# CNEPuckRevG_Drivers_1.net
KiCad netlist of a schematic drawn in Altium Designer
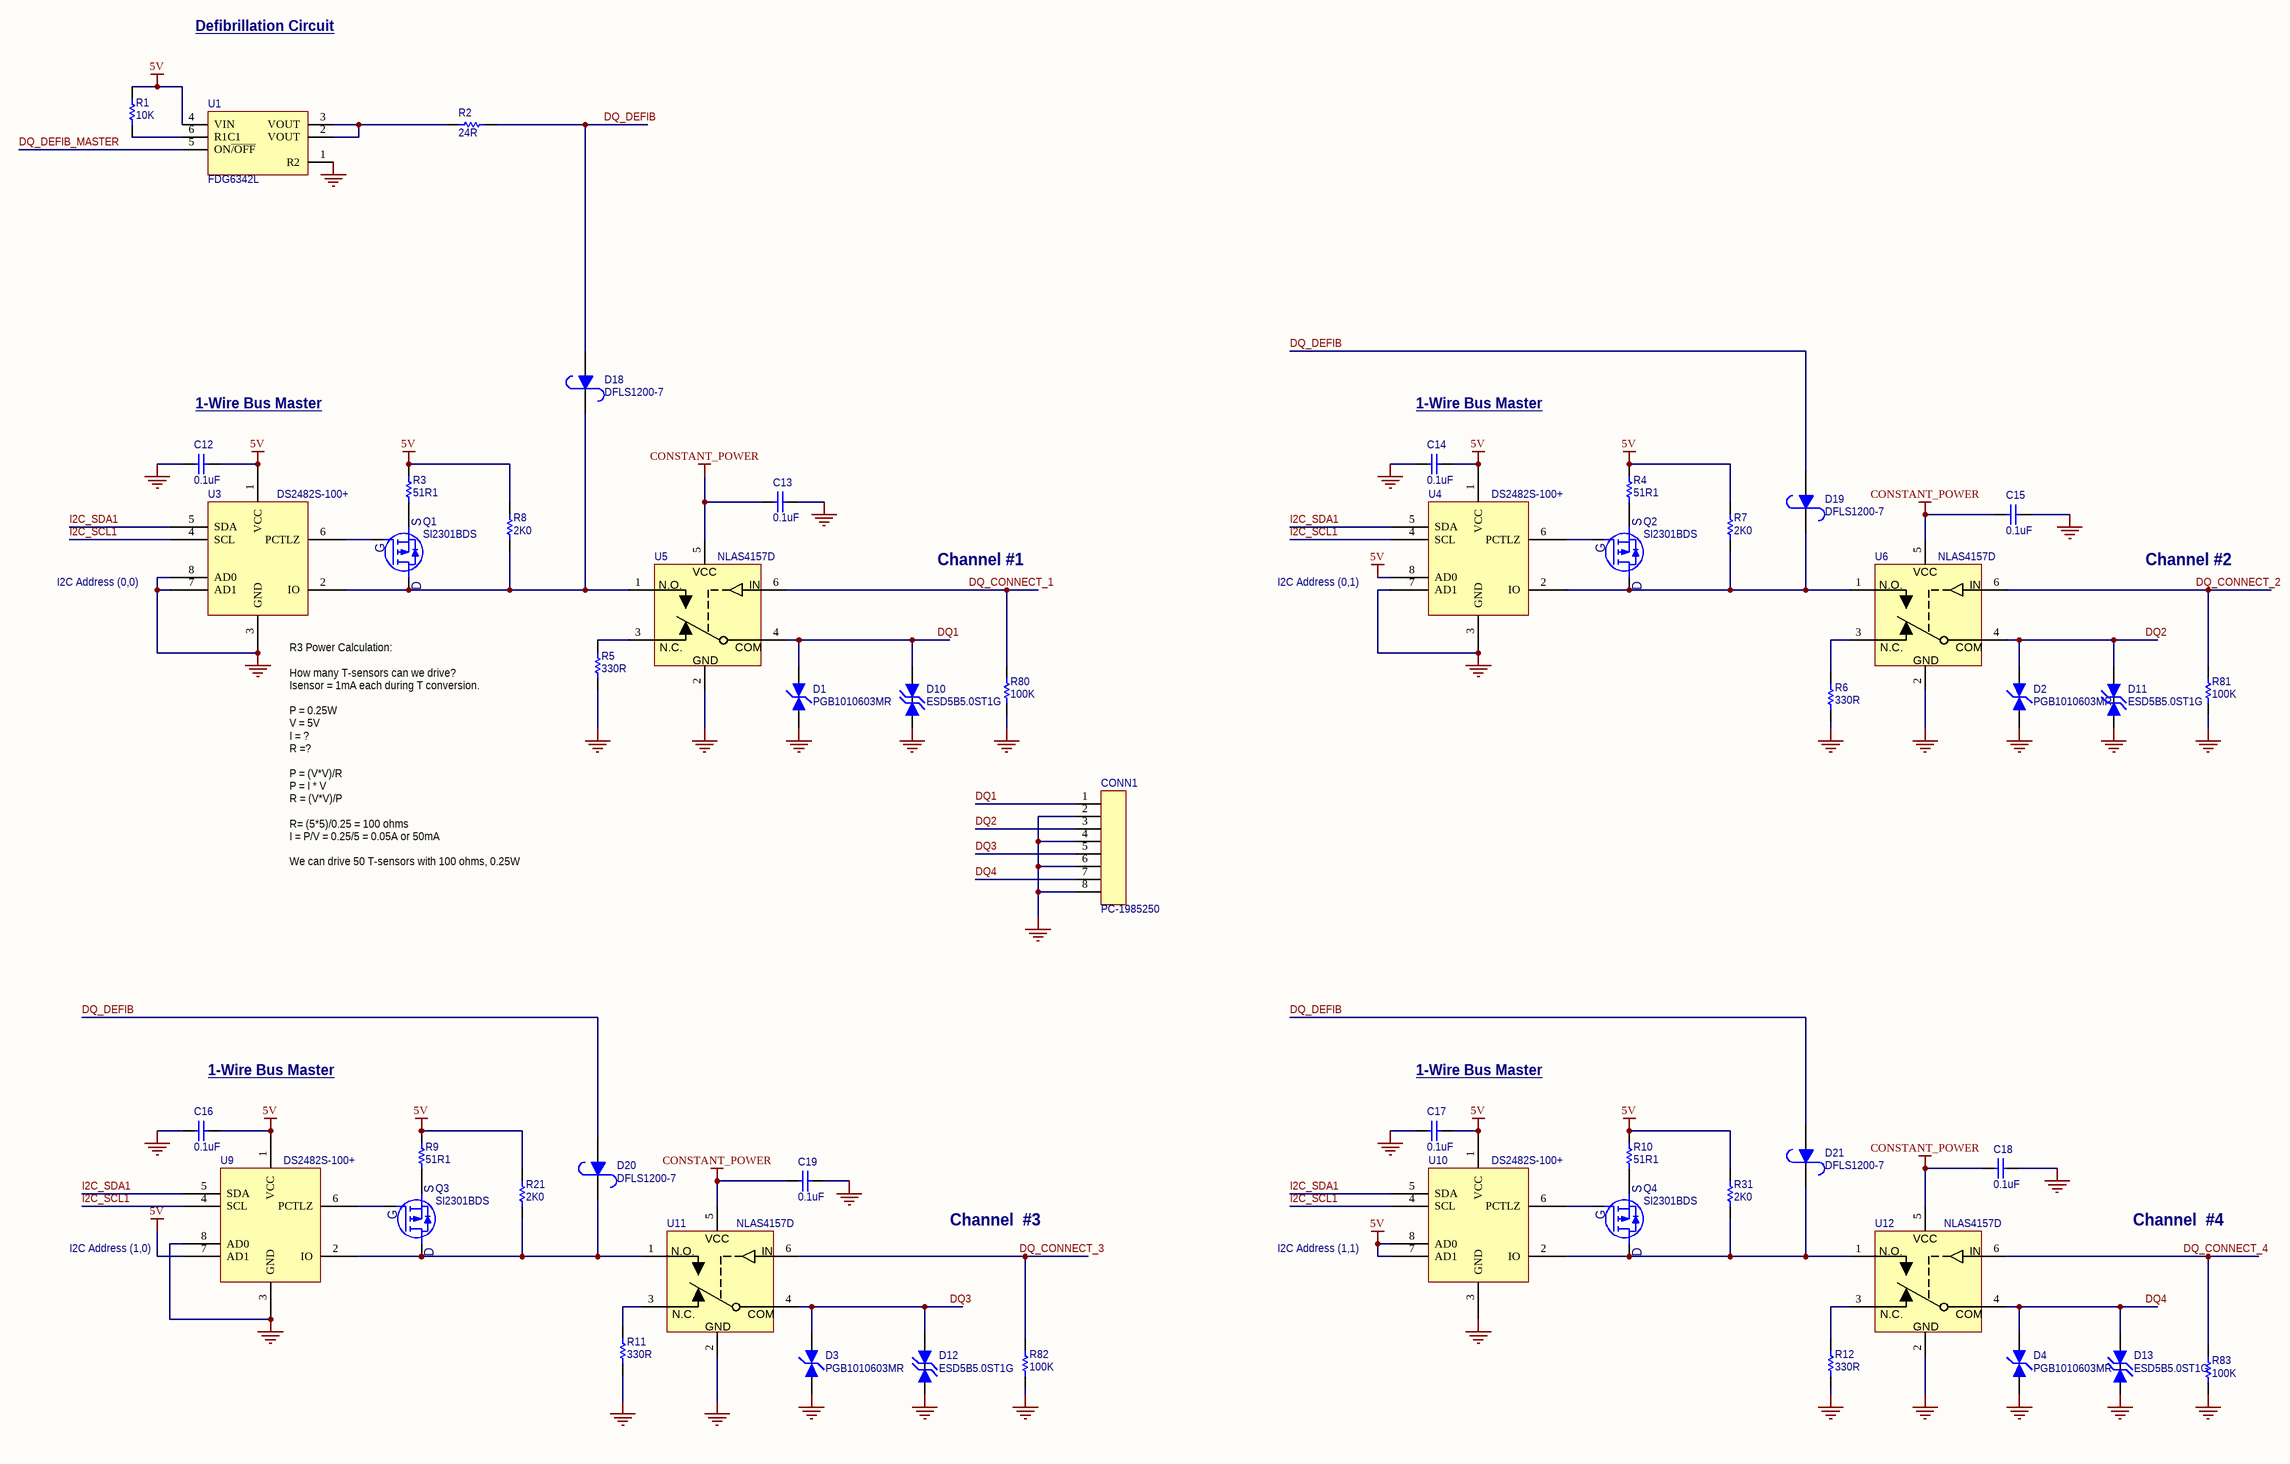
[diagram p0: CNEPuckRevG_Drivers_1.SchDoc]

(export (version "E")
  (design (tool "Eeschema 10.0.6"))
  (components
    (comp (ref "C12")
      (value "0.1uF")
      (footprint "RC0603")
      (description "CAP CERM .1UF 10% 16V X7R 0603")
      (fields (field (name "TOLERANCE") "±10%") (field (name "MANUFACTURER PART NUMBER") "0603YC104KAT2A"))
      (libsource (lib "Swage") (part "0603YC104KAT2A"))
    )
    (comp (ref "C13")
      (value "0.1uF")
      (footprint "RC0603")
      (description "CAP CERM .1UF 10% 16V X7R 0603")
      (fields (field (name "TOLERANCE") "±10%") (field (name "MANUFACTURER PART NUMBER") "0603YC104KAT2A"))
      (libsource (lib "Swage") (part "0603YC104KAT2A"))
    )
    (comp (ref "C14")
      (value "0.1uF")
      (footprint "RC0603")
      (description "CAP CERM .1UF 10% 16V X7R 0603")
      (fields (field (name "TOLERANCE") "±10%") (field (name "MANUFACTURER PART NUMBER") "0603YC104KAT2A"))
      (libsource (lib "Swage") (part "0603YC104KAT2A"))
    )
    (comp (ref "C15")
      (value "0.1uF")
      (footprint "RC0603")
      (description "CAP CERM .1UF 10% 16V X7R 0603")
      (fields (field (name "TOLERANCE") "±10%") (field (name "MANUFACTURER PART NUMBER") "0603YC104KAT2A"))
      (libsource (lib "Swage") (part "0603YC104KAT2A"))
    )
    (comp (ref "C16")
      (value "0.1uF")
      (footprint "RC0603")
      (description "CAP CERM .1UF 10% 16V X7R 0603")
      (fields (field (name "TOLERANCE") "±10%") (field (name "MANUFACTURER PART NUMBER") "0603YC104KAT2A"))
      (libsource (lib "Swage") (part "0603YC104KAT2A"))
    )
    (comp (ref "C17")
      (value "0.1uF")
      (footprint "RC0603")
      (description "CAP CERM .1UF 10% 16V X7R 0603")
      (fields (field (name "TOLERANCE") "±10%") (field (name "MANUFACTURER PART NUMBER") "0603YC104KAT2A"))
      (libsource (lib "Swage") (part "0603YC104KAT2A"))
    )
    (comp (ref "C18")
      (value "0.1uF")
      (footprint "RC0603")
      (description "CAP CERM .1UF 10% 16V X7R 0603")
      (fields (field (name "TOLERANCE") "±10%") (field (name "MANUFACTURER PART NUMBER") "0603YC104KAT2A"))
      (libsource (lib "Swage") (part "0603YC104KAT2A"))
    )
    (comp (ref "C19")
      (value "0.1uF")
      (footprint "RC0603")
      (description "CAP CERM .1UF 10% 16V X7R 0603")
      (fields (field (name "TOLERANCE") "±10%") (field (name "MANUFACTURER PART NUMBER") "0603YC104KAT2A"))
      (libsource (lib "Swage") (part "0603YC104KAT2A"))
    )
    (comp (ref "CONN1")
      (value "PC-1985250")
      (footprint "PTSA1.5/8-3.5-Z")
      (description "TERM BLOCK PCB 8POS 3.5MM GREEN")
      (fields
        (field (name "MANUFACTURER") "Phoenix Contact")
        (field (name "MANUFACTURER PART NUMBER") "1985250")
      )
      (libsource (lib "Swage") (part "1985250"))
    )
    (comp (ref "D1")
      (value "PGB1010603MR")
      (footprint "RC0603")
      (description "SUPPRESSOR ESD 24VDC 0603 SMD")
      (fields (field (name "MANUFACTURER") "Littelfuse Inc"))
      (libsource (lib "Swage") (part "PGB1010603MR"))
    )
    (comp (ref "D2")
      (value "PGB1010603MR")
      (footprint "RC0603")
      (description "SUPPRESSOR ESD 24VDC 0603 SMD")
      (fields (field (name "MANUFACTURER") "Littelfuse Inc"))
      (libsource (lib "Swage") (part "PGB1010603MR"))
    )
    (comp (ref "D3")
      (value "PGB1010603MR")
      (footprint "RC0603")
      (description "SUPPRESSOR ESD 24VDC 0603 SMD")
      (fields (field (name "MANUFACTURER") "Littelfuse Inc"))
      (libsource (lib "Swage") (part "PGB1010603MR"))
    )
    (comp (ref "D4")
      (value "PGB1010603MR")
      (footprint "RC0603")
      (description "SUPPRESSOR ESD 24VDC 0603 SMD")
      (fields (field (name "MANUFACTURER") "Littelfuse Inc"))
      (libsource (lib "Swage") (part "PGB1010603MR"))
    )
    (comp (ref "D10")
      (value "ESD5B5.0ST1G")
      (footprint "SOD-523")
      (description "TVS BIDIRECT 50W SOD523")
      (fields (field (name "MANUFACTURER") "ON Semiconductor"))
      (libsource (lib "Swage") (part "ESD5B5.0ST1G"))
    )
    (comp (ref "D11")
      (value "ESD5B5.0ST1G")
      (footprint "SOD-523")
      (description "TVS BIDIRECT 50W SOD523")
      (fields (field (name "MANUFACTURER") "ON Semiconductor"))
      (libsource (lib "Swage") (part "ESD5B5.0ST1G"))
    )
    (comp (ref "D12")
      (value "ESD5B5.0ST1G")
      (footprint "SOD-523")
      (description "TVS BIDIRECT 50W SOD523")
      (fields (field (name "MANUFACTURER") "ON Semiconductor"))
      (libsource (lib "Swage") (part "ESD5B5.0ST1G"))
    )
    (comp (ref "D13")
      (value "ESD5B5.0ST1G")
      (footprint "SOD-523")
      (description "TVS BIDIRECT 50W SOD523")
      (fields (field (name "MANUFACTURER") "ON Semiconductor"))
      (libsource (lib "Swage") (part "ESD5B5.0ST1G"))
    )
    (comp (ref "D18")
      (value "DFLS1200-7")
      (footprint "POWERDI-123")
      (description "DIODE SCHOTTKY 1A 200V PWRDI 123")
      (fields (field (name "MANUFACTURER") "Diodes Inc"))
      (libsource (lib "Swage") (part "DFLS1200-7"))
    )
    (comp (ref "D19")
      (value "DFLS1200-7")
      (footprint "POWERDI-123")
      (description "DIODE SCHOTTKY 1A 200V PWRDI 123")
      (fields (field (name "MANUFACTURER") "Diodes Inc"))
      (libsource (lib "Swage") (part "DFLS1200-7"))
    )
    (comp (ref "D20")
      (value "DFLS1200-7")
      (footprint "POWERDI-123")
      (description "DIODE SCHOTTKY 1A 200V PWRDI 123")
      (fields (field (name "MANUFACTURER") "Diodes Inc"))
      (libsource (lib "Swage") (part "DFLS1200-7"))
    )
    (comp (ref "D21")
      (value "DFLS1200-7")
      (footprint "POWERDI-123")
      (description "DIODE SCHOTTKY 1A 200V PWRDI 123")
      (fields (field (name "MANUFACTURER") "Diodes Inc"))
      (libsource (lib "Swage") (part "DFLS1200-7"))
    )
    (comp (ref "Q1")
      (value "SI2301BDS")
      (footprint "SOT23(DGS)")
      (description "MOSFET P-CH 20V 2.2A SOT23-3")
      (fields
        (field (name "MANUFACTURER") "Vishay/Siliconix")
        (field (name "MANUFACTURER PART NUMBER") "SI2301BDS-T1-E3")
      )
      (libsource (lib "Swage") (part "SI2301BDS-T1-E3"))
    )
    (comp (ref "Q2")
      (value "SI2301BDS")
      (footprint "SOT23(DGS)")
      (description "MOSFET P-CH 20V 2.2A SOT23-3")
      (fields
        (field (name "MANUFACTURER") "Vishay/Siliconix")
        (field (name "MANUFACTURER PART NUMBER") "SI2301BDS-T1-E3")
      )
      (libsource (lib "Swage") (part "SI2301BDS-T1-E3"))
    )
    (comp (ref "Q3")
      (value "SI2301BDS")
      (footprint "SOT23(DGS)")
      (description "MOSFET P-CH 20V 2.2A SOT23-3")
      (fields
        (field (name "MANUFACTURER") "Vishay/Siliconix")
        (field (name "MANUFACTURER PART NUMBER") "SI2301BDS-T1-E3")
      )
      (libsource (lib "Swage") (part "SI2301BDS-T1-E3"))
    )
    (comp (ref "Q4")
      (value "SI2301BDS")
      (footprint "SOT23(DGS)")
      (description "MOSFET P-CH 20V 2.2A SOT23-3")
      (fields
        (field (name "MANUFACTURER") "Vishay/Siliconix")
        (field (name "MANUFACTURER PART NUMBER") "SI2301BDS-T1-E3")
      )
      (libsource (lib "Swage") (part "SI2301BDS-T1-E3"))
    )
    (comp (ref "R1")
      (value "10K")
      (footprint "RC0603")
      (description "RES 10K OHM 1/10W 5% 0603 SMD")
      (fields
        (field (name "MANUFACTURER") "Panasonic Electronic Components")
        (field (name "MANUFACTURER PART NUMBER") "ERJ-3GEYJ103V")
      )
      (libsource (lib "Swage") (part "ERJ-3GEYJ103V"))
    )
    (comp (ref "R2")
      (value "24R")
      (footprint "RES2512")
      (description "RES 24 OHM 1W 5% 2512 SMD")
      (fields
        (field (name "MANUFACTURER") "Vishay/Dale")
        (field (name "MANUFACTURER PART NUMBER") "CRCW251224R0JNEG")
      )
      (libsource (lib "Swage") (part "RMCF2512JT24R0"))
    )
    (comp (ref "R3")
      (value "51R1")
      (footprint "RC0603")
      (description "RES 51.1 OHM .25W 1% 0603 SMD")
      (fields
        (field (name "MANUFACTURER") "Vishay Dale")
        (field (name "MANUFACTURER PART NUMBER") "CRCW060351R1FKEAHP")
      )
      (libsource (lib "Swage") (part "CRCW060351R1FKEAHP"))
    )
    (comp (ref "R4")
      (value "51R1")
      (footprint "RC0603")
      (description "RES 51.1 OHM .25W 1% 0603 SMD")
      (fields
        (field (name "MANUFACTURER") "Vishay Dale")
        (field (name "MANUFACTURER PART NUMBER") "CRCW060351R1FKEAHP")
      )
      (libsource (lib "Swage") (part "CRCW060351R1FKEAHP"))
    )
    (comp (ref "R5")
      (value "330R")
      (footprint "RC0805")
      (description "RES 330 OHM 1/8W 5% 0805 SMD")
      (fields
        (field (name "MANUFACTURER") "KOA Speer Technologies")
        (field (name "MANUFACTURER PART NUMBER") "RK73B2ATTD331J")
      )
      (libsource (lib "Swage") (part "ERJ-6GEYJ331V"))
    )
    (comp (ref "R6")
      (value "330R")
      (footprint "RC0805")
      (description "RES 330 OHM 1/8W 5% 0805 SMD")
      (fields
        (field (name "MANUFACTURER") "KOA Speer Technologies")
        (field (name "MANUFACTURER PART NUMBER") "RK73B2ATTD331J")
      )
      (libsource (lib "Swage") (part "ERJ-6GEYJ331V"))
    )
    (comp (ref "R7")
      (value "2K0")
      (footprint "RC0603")
      (description "RES 2K OHM 1/10W 1% 0603 SMD")
      (fields
        (field (name "MANUFACTURER") "Panasonic Electronic Components")
        (field (name "MANUFACTURER PART NUMBER") "ERJ-3EKF2001V")
      )
      (libsource (lib "Swage") (part "ERJ-3EKF2001V"))
    )
    (comp (ref "R8")
      (value "2K0")
      (footprint "RC0603")
      (description "RES 2K OHM 1/10W 1% 0603 SMD")
      (fields
        (field (name "MANUFACTURER") "Panasonic Electronic Components")
        (field (name "MANUFACTURER PART NUMBER") "ERJ-3EKF2001V")
      )
      (libsource (lib "Swage") (part "ERJ-3EKF2001V"))
    )
    (comp (ref "R9")
      (value "51R1")
      (footprint "RC0603")
      (description "RES 51.1 OHM .25W 1% 0603 SMD")
      (fields
        (field (name "MANUFACTURER") "Vishay Dale")
        (field (name "MANUFACTURER PART NUMBER") "CRCW060351R1FKEAHP")
      )
      (libsource (lib "Swage") (part "CRCW060351R1FKEAHP"))
    )
    (comp (ref "R10")
      (value "51R1")
      (footprint "RC0603")
      (description "RES 51.1 OHM .25W 1% 0603 SMD")
      (fields
        (field (name "MANUFACTURER") "Vishay Dale")
        (field (name "MANUFACTURER PART NUMBER") "CRCW060351R1FKEAHP")
      )
      (libsource (lib "Swage") (part "CRCW060351R1FKEAHP"))
    )
    (comp (ref "R11")
      (value "330R")
      (footprint "RC0805")
      (description "RES 330 OHM 1/8W 5% 0805 SMD")
      (fields
        (field (name "MANUFACTURER") "KOA Speer Technologies")
        (field (name "MANUFACTURER PART NUMBER") "RK73B2ATTD331J")
      )
      (libsource (lib "Swage") (part "ERJ-6GEYJ331V"))
    )
    (comp (ref "R12")
      (value "330R")
      (footprint "RC0805")
      (description "RES 330 OHM 1/8W 5% 0805 SMD")
      (fields
        (field (name "MANUFACTURER") "KOA Speer Technologies")
        (field (name "MANUFACTURER PART NUMBER") "RK73B2ATTD331J")
      )
      (libsource (lib "Swage") (part "ERJ-6GEYJ331V"))
    )
    (comp (ref "R21")
      (value "2K0")
      (footprint "RC0603")
      (description "RES 2K OHM 1/10W 1% 0603 SMD")
      (fields
        (field (name "MANUFACTURER") "Panasonic Electronic Components")
        (field (name "MANUFACTURER PART NUMBER") "ERJ-3EKF2001V")
      )
      (libsource (lib "Swage") (part "ERJ-3EKF2001V"))
    )
    (comp (ref "R31")
      (value "2K0")
      (footprint "RC0603")
      (description "RES 2K OHM 1/10W 1% 0603 SMD")
      (fields
        (field (name "MANUFACTURER") "Panasonic Electronic Components")
        (field (name "MANUFACTURER PART NUMBER") "ERJ-3EKF2001V")
      )
      (libsource (lib "Swage") (part "ERJ-3EKF2001V"))
    )
    (comp (ref "R80")
      (value "100K")
      (footprint "RC0603")
      (description "RES 100K OHM 1/10W 5% 0603 SMD")
      (fields
        (field (name "MANUFACTURER") "Panasonic Electronic Components")
        (field (name "MANUFACTURER PART NUMBER") "ERJ-3GEYJ104V")
      )
      (libsource (lib "Swage") (part "ERJ-3GEYJ104V"))
    )
    (comp (ref "R81")
      (value "100K")
      (footprint "RC0603")
      (description "RES 100K OHM 1/10W 5% 0603 SMD")
      (fields
        (field (name "MANUFACTURER") "Panasonic Electronic Components")
        (field (name "MANUFACTURER PART NUMBER") "ERJ-3GEYJ104V")
      )
      (libsource (lib "Swage") (part "ERJ-3GEYJ104V"))
    )
    (comp (ref "R82")
      (value "100K")
      (footprint "RC0603")
      (description "RES 100K OHM 1/10W 5% 0603 SMD")
      (fields
        (field (name "MANUFACTURER") "Panasonic Electronic Components")
        (field (name "MANUFACTURER PART NUMBER") "ERJ-3GEYJ104V")
      )
      (libsource (lib "Swage") (part "ERJ-3GEYJ104V"))
    )
    (comp (ref "R83")
      (value "100K")
      (footprint "RC0603")
      (description "RES 100K OHM 1/10W 5% 0603 SMD")
      (fields
        (field (name "MANUFACTURER") "Panasonic Electronic Components")
        (field (name "MANUFACTURER PART NUMBER") "ERJ-3GEYJ104V")
      )
      (libsource (lib "Swage") (part "ERJ-3GEYJ104V"))
    )
    (comp (ref "U1")
      (value "FDG6342L")
      (footprint "TS5A3160")
      (description "IC LOAD SWITCH INTEGRATED SC70-6")
      (fields (field (name "MANUFACTURER") "Fairchild Semiconductor"))
      (libsource (lib "Swage") (part "FDG6342L"))
    )
    (comp (ref "U3")
      (value "DS2482S-100+")
      (footprint "SOIC127P580X153-8N")
      (description "IC BRIDGE I2C TO 1-WIRE 8-SOIC")
      (fields (field (name "MANUFACTURER") "Maxim Integrated"))
      (libsource (lib "Swage") (part "DS2482S-100+"))
    )
    (comp (ref "U4")
      (value "DS2482S-100+")
      (footprint "SOIC127P580X153-8N")
      (description "IC BRIDGE I2C TO 1-WIRE 8-SOIC")
      (fields (field (name "MANUFACTURER") "Maxim Integrated"))
      (libsource (lib "Swage") (part "DS2482S-100+"))
    )
    (comp (ref "U5")
      (value "NLAS4157D")
      (footprint "TS5A3160")
      (description "IC SWITCH SPDT SC88")
      (fields
        (field (name "MANUFACTURER") "ON Semiconductor")
        (field (name "MANUFACTURER PART NUMBER") "NLAS4157DFT2G")
      )
      (libsource (lib "Swage") (part "NLAS4157DFT2G"))
    )
    (comp (ref "U6")
      (value "NLAS4157D")
      (footprint "TS5A3160")
      (description "IC SWITCH SPDT SC88")
      (fields
        (field (name "MANUFACTURER") "ON Semiconductor")
        (field (name "MANUFACTURER PART NUMBER") "NLAS4157DFT2G")
      )
      (libsource (lib "Swage") (part "NLAS4157DFT2G"))
    )
    (comp (ref "U9")
      (value "DS2482S-100+")
      (footprint "SOIC127P580X153-8N")
      (description "IC BRIDGE I2C TO 1-WIRE 8-SOIC")
      (fields (field (name "MANUFACTURER") "Maxim Integrated"))
      (libsource (lib "Swage") (part "DS2482S-100+"))
    )
    (comp (ref "U10")
      (value "DS2482S-100+")
      (footprint "SOIC127P580X153-8N")
      (description "IC BRIDGE I2C TO 1-WIRE 8-SOIC")
      (fields (field (name "MANUFACTURER") "Maxim Integrated"))
      (libsource (lib "Swage") (part "DS2482S-100+"))
    )
    (comp (ref "U11")
      (value "NLAS4157D")
      (footprint "TS5A3160")
      (description "IC SWITCH SPDT SC88")
      (fields
        (field (name "MANUFACTURER") "ON Semiconductor")
        (field (name "MANUFACTURER PART NUMBER") "NLAS4157DFT2G")
      )
      (libsource (lib "Swage") (part "NLAS4157DFT2G"))
    )
    (comp (ref "U12")
      (value "NLAS4157D")
      (footprint "TS5A3160")
      (description "IC SWITCH SPDT SC88")
      (fields
        (field (name "MANUFACTURER") "ON Semiconductor")
        (field (name "MANUFACTURER PART NUMBER") "NLAS4157DFT2G")
      )
      (libsource (lib "Swage") (part "NLAS4157DFT2G"))
    )
  )
  (nets
    (net (code "1") (name "/DQ1") (class "Default")
      (node (ref "CONN1") (pin "1") (pinfunction "1_1") (pintype "passive"))
      (node (ref "D1") (pin "2") (pinfunction "2_2") (pintype "passive"))
      (node (ref "D10") (pin "2") (pinfunction "2_2") (pintype "passive"))
      (node (ref "U5") (pin "4") (pinfunction "4_4") (pintype "passive"))
    )
    (net (code "2") (name "/DQ2") (class "Default")
      (node (ref "CONN1") (pin "3") (pinfunction "3_3") (pintype "passive"))
      (node (ref "D11") (pin "2") (pinfunction "2_2") (pintype "passive"))
      (node (ref "D2") (pin "2") (pinfunction "2_2") (pintype "passive"))
      (node (ref "U6") (pin "4") (pinfunction "4_4") (pintype "passive"))
    )
    (net (code "3") (name "/DQ3") (class "Default")
      (node (ref "CONN1") (pin "5") (pinfunction "5_5") (pintype "passive"))
      (node (ref "D12") (pin "2") (pinfunction "2_2") (pintype "passive"))
      (node (ref "D3") (pin "2") (pinfunction "2_2") (pintype "passive"))
      (node (ref "U11") (pin "4") (pinfunction "4_4") (pintype "passive"))
    )
    (net (code "4") (name "/DQ4") (class "Default")
      (node (ref "CONN1") (pin "7") (pinfunction "7_7") (pintype "passive"))
      (node (ref "D13") (pin "2") (pinfunction "2_2") (pintype "passive"))
      (node (ref "D4") (pin "2") (pinfunction "2_2") (pintype "passive"))
      (node (ref "U12") (pin "4") (pinfunction "4_4") (pintype "passive"))
    )
    (net (code "5") (name "/DQ_CONNECT_1") (class "Default")
      (node (ref "R80") (pin "1") (pinfunction "1_1") (pintype "passive"))
      (node (ref "U5") (pin "6") (pinfunction "6_6") (pintype "passive"))
    )
    (net (code "6") (name "/DQ_CONNECT_2") (class "Default")
      (node (ref "R81") (pin "1") (pinfunction "1_1") (pintype "passive"))
      (node (ref "U6") (pin "6") (pinfunction "6_6") (pintype "passive"))
    )
    (net (code "7") (name "/DQ_CONNECT_3") (class "Default")
      (node (ref "R82") (pin "1") (pinfunction "1_1") (pintype "passive"))
      (node (ref "U11") (pin "6") (pinfunction "6_6") (pintype "passive"))
    )
    (net (code "8") (name "/DQ_CONNECT_4") (class "Default")
      (node (ref "R83") (pin "1") (pinfunction "1_1") (pintype "passive"))
      (node (ref "U12") (pin "6") (pinfunction "6_6") (pintype "passive"))
    )
    (net (code "9") (name "/DQ_DEFIB") (class "Default")
      (node (ref "D18") (pin "1") (pinfunction "A_1") (pintype "passive"))
      (node (ref "D19") (pin "1") (pinfunction "A_1") (pintype "passive"))
      (node (ref "D20") (pin "1") (pinfunction "A_1") (pintype "passive"))
      (node (ref "D21") (pin "1") (pinfunction "A_1") (pintype "passive"))
      (node (ref "R2") (pin "2") (pinfunction "2_2") (pintype "passive"))
    )
    (net (code "10") (name "/DQ_DEFIB_MASTER") (class "Default")
      (node (ref "U1") (pin "5") (pinfunction "ON~{/OFF}_5") (pintype "passive"))
    )
    (net (code "11") (name "/I2C_SCL1") (class "Default")
      (node (ref "U10") (pin "4") (pinfunction "SCL_4") (pintype "passive"))
      (node (ref "U3") (pin "4") (pinfunction "SCL_4") (pintype "passive"))
      (node (ref "U4") (pin "4") (pinfunction "SCL_4") (pintype "passive"))
      (node (ref "U9") (pin "4") (pinfunction "SCL_4") (pintype "passive"))
    )
    (net (code "12") (name "/I2C_SDA1") (class "Default")
      (node (ref "U10") (pin "5") (pinfunction "SDA_5") (pintype "passive"))
      (node (ref "U3") (pin "5") (pinfunction "SDA_5") (pintype "passive"))
      (node (ref "U4") (pin "5") (pinfunction "SDA_5") (pintype "passive"))
      (node (ref "U9") (pin "5") (pinfunction "SDA_5") (pintype "passive"))
    )
    (net (code "13") (name "5V") (class "Default")
      (node (ref "C12") (pin "2") (pinfunction "2_2") (pintype "passive"))
      (node (ref "C14") (pin "2") (pinfunction "2_2") (pintype "passive"))
      (node (ref "C16") (pin "2") (pinfunction "2_2") (pintype "passive"))
      (node (ref "C17") (pin "2") (pinfunction "2_2") (pintype "passive"))
      (node (ref "R1") (pin "1") (pinfunction "1_1") (pintype "passive"))
      (node (ref "R10") (pin "1") (pinfunction "1_1") (pintype "passive"))
      (node (ref "R21") (pin "1") (pinfunction "1_1") (pintype "passive"))
      (node (ref "R3") (pin "1") (pinfunction "1_1") (pintype "passive"))
      (node (ref "R31") (pin "1") (pinfunction "1_1") (pintype "passive"))
      (node (ref "R4") (pin "1") (pinfunction "1_1") (pintype "passive"))
      (node (ref "R7") (pin "1") (pinfunction "1_1") (pintype "passive"))
      (node (ref "R8") (pin "1") (pinfunction "1_1") (pintype "passive"))
      (node (ref "R9") (pin "1") (pinfunction "1_1") (pintype "passive"))
      (node (ref "U1") (pin "4") (pinfunction "VIN_4") (pintype "passive"))
      (node (ref "U10") (pin "1") (pinfunction "VCC_1") (pintype "passive"))
      (node (ref "U10") (pin "7") (pinfunction "AD1_7") (pintype "passive"))
      (node (ref "U10") (pin "8") (pinfunction "AD0_8") (pintype "passive"))
      (node (ref "U3") (pin "1") (pinfunction "VCC_1") (pintype "passive"))
      (node (ref "U4") (pin "1") (pinfunction "VCC_1") (pintype "passive"))
      (node (ref "U4") (pin "8") (pinfunction "AD0_8") (pintype "passive"))
      (node (ref "U9") (pin "1") (pinfunction "VCC_1") (pintype "passive"))
      (node (ref "U9") (pin "7") (pinfunction "AD1_7") (pintype "passive"))
    )
    (net (code "14") (name "CONSTANT_POWER") (class "Default")
      (node (ref "C13") (pin "1") (pinfunction "1_1") (pintype "passive"))
      (node (ref "C15") (pin "1") (pinfunction "1_1") (pintype "passive"))
      (node (ref "C18") (pin "1") (pinfunction "1_1") (pintype "passive"))
      (node (ref "C19") (pin "1") (pinfunction "1_1") (pintype "passive"))
      (node (ref "U11") (pin "5") (pinfunction "5_5") (pintype "passive"))
      (node (ref "U12") (pin "5") (pinfunction "5_5") (pintype "passive"))
      (node (ref "U5") (pin "5") (pinfunction "5_5") (pintype "passive"))
      (node (ref "U6") (pin "5") (pinfunction "5_5") (pintype "passive"))
    )
    (net (code "15") (name "GND") (class "Default")
      (node (ref "C12") (pin "1") (pinfunction "1_1") (pintype "passive"))
      (node (ref "C13") (pin "2") (pinfunction "2_2") (pintype "passive"))
      (node (ref "C14") (pin "1") (pinfunction "1_1") (pintype "passive"))
      (node (ref "C15") (pin "2") (pinfunction "2_2") (pintype "passive"))
      (node (ref "C16") (pin "1") (pinfunction "1_1") (pintype "passive"))
      (node (ref "C17") (pin "1") (pinfunction "1_1") (pintype "passive"))
      (node (ref "C18") (pin "2") (pinfunction "2_2") (pintype "passive"))
      (node (ref "C19") (pin "2") (pinfunction "2_2") (pintype "passive"))
      (node (ref "CONN1") (pin "2") (pinfunction "2_2") (pintype "passive"))
      (node (ref "CONN1") (pin "4") (pinfunction "4_4") (pintype "passive"))
      (node (ref "CONN1") (pin "6") (pinfunction "6_6") (pintype "passive"))
      (node (ref "CONN1") (pin "8") (pinfunction "8_8") (pintype "passive"))
      (node (ref "D1") (pin "1") (pintype "passive"))
      (node (ref "D10") (pin "1") (pintype "passive"))
      (node (ref "D11") (pin "1") (pintype "passive"))
      (node (ref "D12") (pin "1") (pintype "passive"))
      (node (ref "D13") (pin "1") (pintype "passive"))
      (node (ref "D2") (pin "1") (pintype "passive"))
      (node (ref "D3") (pin "1") (pintype "passive"))
      (node (ref "D4") (pin "1") (pintype "passive"))
      (node (ref "R11") (pin "2") (pinfunction "2_2") (pintype "passive"))
      (node (ref "R12") (pin "2") (pinfunction "2_2") (pintype "passive"))
      (node (ref "R5") (pin "2") (pinfunction "2_2") (pintype "passive"))
      (node (ref "R6") (pin "2") (pinfunction "2_2") (pintype "passive"))
      (node (ref "R80") (pin "2") (pinfunction "2_2") (pintype "passive"))
      (node (ref "R81") (pin "2") (pinfunction "2_2") (pintype "passive"))
      (node (ref "R82") (pin "2") (pinfunction "2_2") (pintype "passive"))
      (node (ref "R83") (pin "2") (pinfunction "2_2") (pintype "passive"))
      (node (ref "U1") (pin "1") (pinfunction "R2_1") (pintype "passive"))
      (node (ref "U10") (pin "3") (pinfunction "GND_3") (pintype "passive"))
      (node (ref "U11") (pin "2") (pinfunction "GND_2") (pintype "passive"))
      (node (ref "U12") (pin "2") (pinfunction "GND_2") (pintype "passive"))
      (node (ref "U3") (pin "3") (pinfunction "GND_3") (pintype "passive"))
      (node (ref "U3") (pin "7") (pinfunction "AD1_7") (pintype "passive"))
      (node (ref "U3") (pin "8") (pinfunction "AD0_8") (pintype "passive"))
      (node (ref "U4") (pin "3") (pinfunction "GND_3") (pintype "passive"))
      (node (ref "U4") (pin "7") (pinfunction "AD1_7") (pintype "passive"))
      (node (ref "U5") (pin "2") (pinfunction "GND_2") (pintype "passive"))
      (node (ref "U6") (pin "2") (pinfunction "GND_2") (pintype "passive"))
      (node (ref "U9") (pin "3") (pinfunction "GND_3") (pintype "passive"))
      (node (ref "U9") (pin "8") (pinfunction "AD0_8") (pintype "passive"))
    )
    (net (code "16") (name "Net-(D18-K)") (class "Default")
      (node (ref "D18") (pin "2") (pinfunction "K_2") (pintype "passive"))
      (node (ref "Q1") (pin "D") (pinfunction "D_D") (pintype "passive"))
      (node (ref "R8") (pin "2") (pinfunction "2_2") (pintype "passive"))
      (node (ref "U3") (pin "2") (pinfunction "IO_2") (pintype "passive"))
      (node (ref "U5") (pin "1") (pinfunction "NO_1") (pintype "passive"))
    )
    (net (code "17") (name "Net-(D19-K)") (class "Default")
      (node (ref "D19") (pin "2") (pinfunction "K_2") (pintype "passive"))
      (node (ref "Q2") (pin "D") (pinfunction "D_D") (pintype "passive"))
      (node (ref "R7") (pin "2") (pinfunction "2_2") (pintype "passive"))
      (node (ref "U4") (pin "2") (pinfunction "IO_2") (pintype "passive"))
      (node (ref "U6") (pin "1") (pinfunction "NO_1") (pintype "passive"))
    )
    (net (code "18") (name "Net-(D20-K)") (class "Default")
      (node (ref "D20") (pin "2") (pinfunction "K_2") (pintype "passive"))
      (node (ref "Q3") (pin "D") (pinfunction "D_D") (pintype "passive"))
      (node (ref "R21") (pin "2") (pinfunction "2_2") (pintype "passive"))
      (node (ref "U11") (pin "1") (pinfunction "NO_1") (pintype "passive"))
      (node (ref "U9") (pin "2") (pinfunction "IO_2") (pintype "passive"))
    )
    (net (code "19") (name "Net-(D21-K)") (class "Default")
      (node (ref "D21") (pin "2") (pinfunction "K_2") (pintype "passive"))
      (node (ref "Q4") (pin "D") (pinfunction "D_D") (pintype "passive"))
      (node (ref "R31") (pin "2") (pinfunction "2_2") (pintype "passive"))
      (node (ref "U10") (pin "2") (pinfunction "IO_2") (pintype "passive"))
      (node (ref "U12") (pin "1") (pinfunction "NO_1") (pintype "passive"))
    )
    (net (code "20") (name "Net-(Q1-PadS)") (class "Default")
      (node (ref "Q1") (pin "S") (pinfunction "S_S") (pintype "passive"))
      (node (ref "R3") (pin "2") (pinfunction "2_2") (pintype "passive"))
    )
    (net (code "21") (name "Net-(Q2-PadS)") (class "Default")
      (node (ref "Q2") (pin "S") (pinfunction "S_S") (pintype "passive"))
      (node (ref "R4") (pin "2") (pinfunction "2_2") (pintype "passive"))
    )
    (net (code "22") (name "Net-(Q3-PadS)") (class "Default")
      (node (ref "Q3") (pin "S") (pinfunction "S_S") (pintype "passive"))
      (node (ref "R9") (pin "2") (pinfunction "2_2") (pintype "passive"))
    )
    (net (code "23") (name "Net-(Q4-PadS)") (class "Default")
      (node (ref "Q4") (pin "S") (pinfunction "S_S") (pintype "passive"))
      (node (ref "R10") (pin "2") (pinfunction "2_2") (pintype "passive"))
    )
    (net (code "24") (name "Net-(R2-Pad1)") (class "Default")
      (node (ref "R2") (pin "1") (pinfunction "1_1") (pintype "passive"))
      (node (ref "U1") (pin "2") (pinfunction "VOUT_2") (pintype "passive"))
      (node (ref "U1") (pin "3") (pinfunction "VOUT_3") (pintype "passive"))
    )
    (net (code "25") (name "Net-(U1-R1C1)") (class "Default")
      (node (ref "R1") (pin "2") (pinfunction "2_2") (pintype "passive"))
      (node (ref "U1") (pin "6") (pinfunction "R1C1_6") (pintype "passive"))
    )
    (net (code "26") (name "Net-(U3-PCTLZ)") (class "Default")
      (node (ref "Q1") (pin "G") (pinfunction "G_G") (pintype "passive"))
      (node (ref "U3") (pin "6") (pinfunction "PCTLZ_6") (pintype "passive"))
    )
    (net (code "27") (name "Net-(U4-PCTLZ)") (class "Default")
      (node (ref "Q2") (pin "G") (pinfunction "G_G") (pintype "passive"))
      (node (ref "U4") (pin "6") (pinfunction "PCTLZ_6") (pintype "passive"))
    )
    (net (code "28") (name "Net-(U5-NC)") (class "Default")
      (node (ref "R5") (pin "1") (pinfunction "1_1") (pintype "passive"))
      (node (ref "U5") (pin "3") (pinfunction "NC_3") (pintype "passive"))
    )
    (net (code "29") (name "Net-(U6-NC)") (class "Default")
      (node (ref "R6") (pin "1") (pinfunction "1_1") (pintype "passive"))
      (node (ref "U6") (pin "3") (pinfunction "NC_3") (pintype "passive"))
    )
    (net (code "30") (name "Net-(U9-PCTLZ)") (class "Default")
      (node (ref "Q3") (pin "G") (pinfunction "G_G") (pintype "passive"))
      (node (ref "U9") (pin "6") (pinfunction "PCTLZ_6") (pintype "passive"))
    )
    (net (code "31") (name "Net-(U10-PCTLZ)") (class "Default")
      (node (ref "Q4") (pin "G") (pinfunction "G_G") (pintype "passive"))
      (node (ref "U10") (pin "6") (pinfunction "PCTLZ_6") (pintype "passive"))
    )
    (net (code "32") (name "Net-(U11-NC)") (class "Default")
      (node (ref "R11") (pin "1") (pinfunction "1_1") (pintype "passive"))
      (node (ref "U11") (pin "3") (pinfunction "NC_3") (pintype "passive"))
    )
    (net (code "33") (name "Net-(U12-NC)") (class "Default")
      (node (ref "R12") (pin "1") (pinfunction "1_1") (pintype "passive"))
      (node (ref "U12") (pin "3") (pinfunction "NC_3") (pintype "passive"))
    )
  )
)
